# Led_7_Seg_2_3In.net
KiCad netlist of a schematic drawn in Altium Designer
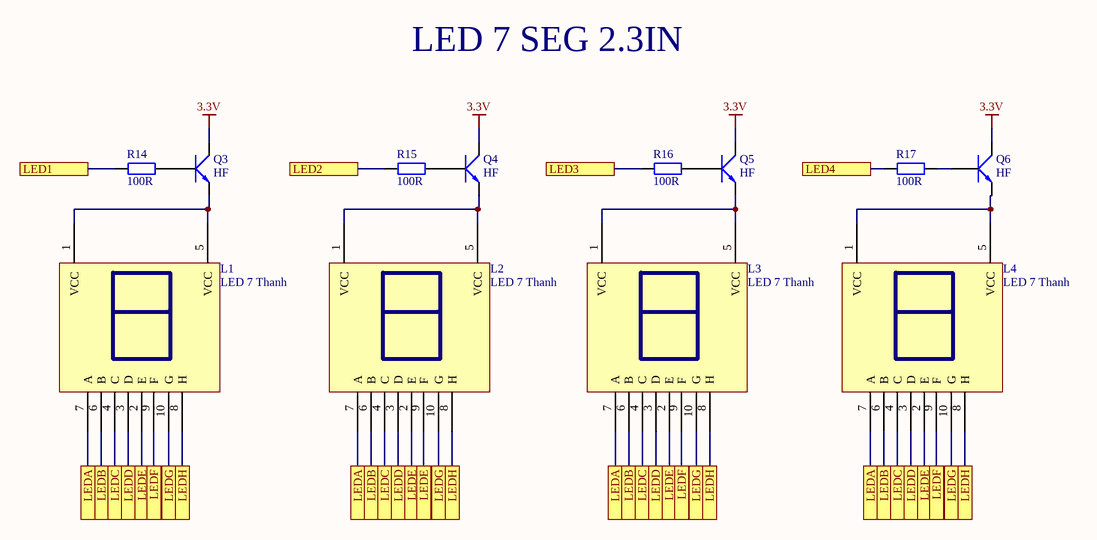
[diagram p0: Led 7 Seg 2.3In.SchDoc]

(export (version "E")
  (design (tool "Eeschema 10.0.6"))
  (components
    (comp (ref "L1")
      (value "LED 7 Thanh")
      (footprint "LED7SEG_2.3inch")
      (description "Dán")
      (libsource (lib "Altium_Lib_by_KhueNguyenCreator") (part "LED 7x1 2.3inch Anot"))
    )
    (comp (ref "L2")
      (value "LED 7 Thanh")
      (footprint "LED7SEG_2.3inch")
      (description "Dán")
      (libsource (lib "Altium_Lib_by_KhueNguyenCreator") (part "LED 7x1 2.3inch Anot"))
    )
    (comp (ref "L3")
      (value "LED 7 Thanh")
      (footprint "LED7SEG_2.3inch")
      (description "Dán")
      (libsource (lib "Altium_Lib_by_KhueNguyenCreator") (part "LED 7x1 2.3inch Anot"))
    )
    (comp (ref "L4")
      (value "LED 7 Thanh")
      (footprint "LED7SEG_2.3inch")
      (description "Dán")
      (libsource (lib "Altium_Lib_by_KhueNguyenCreator") (part "LED 7x1 2.3inch Anot"))
    )
    (comp (ref "Q3")
      (value "HF")
      (footprint "SOT23")
      (description "NPN transistor")
      (libsource (lib "Altium_Lib_by_KhueNguyenCreator") (part "C1815 HF SMD"))
    )
    (comp (ref "Q4")
      (value "HF")
      (footprint "SOT23")
      (description "NPN transistor")
      (libsource (lib "Altium_Lib_by_KhueNguyenCreator") (part "C1815 HF SMD"))
    )
    (comp (ref "Q5")
      (value "HF")
      (footprint "SOT23")
      (description "NPN transistor")
      (libsource (lib "Altium_Lib_by_KhueNguyenCreator") (part "C1815 HF SMD"))
    )
    (comp (ref "Q6")
      (value "HF")
      (footprint "SOT23")
      (description "NPN transistor")
      (libsource (lib "Altium_Lib_by_KhueNguyenCreator") (part "C1815 HF SMD"))
    )
    (comp (ref "R14")
      (value "100R")
      (footprint "tro smd 0603")
      (description "Dán")
      (libsource (lib "Altium_Lib_by_KhueNguyenCreator") (part "Tro 0603 5% 100R"))
    )
    (comp (ref "R15")
      (value "100R")
      (footprint "tro smd 0603")
      (description "Dán")
      (libsource (lib "Altium_Lib_by_KhueNguyenCreator") (part "Tro 0603 5% 100R"))
    )
    (comp (ref "R16")
      (value "100R")
      (footprint "tro smd 0603")
      (description "Dán")
      (libsource (lib "Altium_Lib_by_KhueNguyenCreator") (part "Tro 0603 5% 100R"))
    )
    (comp (ref "R17")
      (value "100R")
      (footprint "tro smd 0603")
      (description "Dán")
      (libsource (lib "Altium_Lib_by_KhueNguyenCreator") (part "Tro 0603 5% 100R"))
    )
  )
  (nets
    (net (code "1") (name "/LED1") (class "Default")
      (node (ref "R14") (pin "1") (pinfunction "1_1") (pintype "passive"))
    )
    (net (code "2") (name "/LED2") (class "Default")
      (node (ref "R15") (pin "1") (pinfunction "1_1") (pintype "passive"))
    )
    (net (code "3") (name "/LED3") (class "Default")
      (node (ref "R16") (pin "1") (pinfunction "1_1") (pintype "passive"))
    )
    (net (code "4") (name "/LED4") (class "Default")
      (node (ref "R17") (pin "1") (pinfunction "1_1") (pintype "passive"))
    )
    (net (code "5") (name "/LEDA") (class "Default")
      (node (ref "L1") (pin "7") (pinfunction "A_7") (pintype "passive"))
      (node (ref "L2") (pin "7") (pinfunction "A_7") (pintype "passive"))
      (node (ref "L3") (pin "7") (pinfunction "A_7") (pintype "passive"))
      (node (ref "L4") (pin "7") (pinfunction "A_7") (pintype "passive"))
    )
    (net (code "6") (name "/LEDB") (class "Default")
      (node (ref "L1") (pin "6") (pinfunction "B_6") (pintype "passive"))
      (node (ref "L2") (pin "6") (pinfunction "B_6") (pintype "passive"))
      (node (ref "L3") (pin "6") (pinfunction "B_6") (pintype "passive"))
      (node (ref "L4") (pin "6") (pinfunction "B_6") (pintype "passive"))
    )
    (net (code "7") (name "/LEDC") (class "Default")
      (node (ref "L1") (pin "4") (pinfunction "C_4") (pintype "passive"))
      (node (ref "L2") (pin "4") (pinfunction "C_4") (pintype "passive"))
      (node (ref "L3") (pin "4") (pinfunction "C_4") (pintype "passive"))
      (node (ref "L4") (pin "4") (pinfunction "C_4") (pintype "passive"))
    )
    (net (code "8") (name "/LEDD") (class "Default")
      (node (ref "L1") (pin "3") (pinfunction "D_3") (pintype "passive"))
      (node (ref "L2") (pin "3") (pinfunction "D_3") (pintype "passive"))
      (node (ref "L3") (pin "3") (pinfunction "D_3") (pintype "passive"))
      (node (ref "L4") (pin "3") (pinfunction "D_3") (pintype "passive"))
    )
    (net (code "9") (name "/LEDE") (class "Default")
      (node (ref "L1") (pin "2") (pinfunction "E_2") (pintype "passive"))
      (node (ref "L2") (pin "2") (pinfunction "E_2") (pintype "passive"))
      (node (ref "L2") (pin "9") (pinfunction "F_9") (pintype "passive"))
      (node (ref "L3") (pin "2") (pinfunction "E_2") (pintype "passive"))
      (node (ref "L4") (pin "2") (pinfunction "E_2") (pintype "passive"))
    )
    (net (code "10") (name "/LEDF") (class "Default")
      (node (ref "L1") (pin "9") (pinfunction "F_9") (pintype "passive"))
      (node (ref "L3") (pin "9") (pinfunction "F_9") (pintype "passive"))
      (node (ref "L4") (pin "9") (pinfunction "F_9") (pintype "passive"))
    )
    (net (code "11") (name "/LEDG") (class "Default")
      (node (ref "L1") (pin "10") (pinfunction "G_10") (pintype "passive"))
      (node (ref "L2") (pin "10") (pinfunction "G_10") (pintype "passive"))
      (node (ref "L3") (pin "10") (pinfunction "G_10") (pintype "passive"))
      (node (ref "L4") (pin "10") (pinfunction "G_10") (pintype "passive"))
    )
    (net (code "12") (name "/LEDH") (class "Default")
      (node (ref "L1") (pin "8") (pinfunction "H_8") (pintype "passive"))
      (node (ref "L2") (pin "8") (pinfunction "H_8") (pintype "passive"))
      (node (ref "L3") (pin "8") (pinfunction "H_8") (pintype "passive"))
      (node (ref "L4") (pin "8") (pinfunction "H_8") (pintype "passive"))
    )
    (net (code "13") (name "3.3V") (class "Default")
      (node (ref "Q3") (pin "3") (pinfunction "C_3") (pintype "passive"))
      (node (ref "Q4") (pin "3") (pinfunction "C_3") (pintype "passive"))
      (node (ref "Q5") (pin "3") (pinfunction "C_3") (pintype "passive"))
      (node (ref "Q6") (pin "3") (pinfunction "C_3") (pintype "passive"))
    )
    (net (code "14") (name "Net-(Q3-B)") (class "Default")
      (node (ref "Q3") (pin "1") (pinfunction "B_1") (pintype "passive"))
      (node (ref "R14") (pin "2") (pinfunction "2_2") (pintype "passive"))
    )
    (net (code "15") (name "Net-(Q3-E)") (class "Default")
      (node (ref "L1") (pin "1") (pinfunction "VCC_1") (pintype "passive"))
      (node (ref "L1") (pin "5") (pinfunction "VCC_5") (pintype "passive"))
      (node (ref "Q3") (pin "2") (pinfunction "E_2") (pintype "passive"))
    )
    (net (code "16") (name "Net-(Q4-B)") (class "Default")
      (node (ref "Q4") (pin "1") (pinfunction "B_1") (pintype "passive"))
      (node (ref "R15") (pin "2") (pinfunction "2_2") (pintype "passive"))
    )
    (net (code "17") (name "Net-(Q4-E)") (class "Default")
      (node (ref "L2") (pin "1") (pinfunction "VCC_1") (pintype "passive"))
      (node (ref "L2") (pin "5") (pinfunction "VCC_5") (pintype "passive"))
      (node (ref "Q4") (pin "2") (pinfunction "E_2") (pintype "passive"))
    )
    (net (code "18") (name "Net-(Q5-B)") (class "Default")
      (node (ref "Q5") (pin "1") (pinfunction "B_1") (pintype "passive"))
      (node (ref "R16") (pin "2") (pinfunction "2_2") (pintype "passive"))
    )
    (net (code "19") (name "Net-(Q5-E)") (class "Default")
      (node (ref "L3") (pin "1") (pinfunction "VCC_1") (pintype "passive"))
      (node (ref "L3") (pin "5") (pinfunction "VCC_5") (pintype "passive"))
      (node (ref "Q5") (pin "2") (pinfunction "E_2") (pintype "passive"))
    )
    (net (code "20") (name "Net-(Q6-B)") (class "Default")
      (node (ref "Q6") (pin "1") (pinfunction "B_1") (pintype "passive"))
      (node (ref "R17") (pin "2") (pinfunction "2_2") (pintype "passive"))
    )
    (net (code "21") (name "Net-(Q6-E)") (class "Default")
      (node (ref "L4") (pin "1") (pinfunction "VCC_1") (pintype "passive"))
      (node (ref "L4") (pin "5") (pinfunction "VCC_5") (pintype "passive"))
      (node (ref "Q6") (pin "2") (pinfunction "E_2") (pintype "passive"))
    )
  )
)
